# controller-board.net
KiCad netlist of a schematic drawn in EAGLE
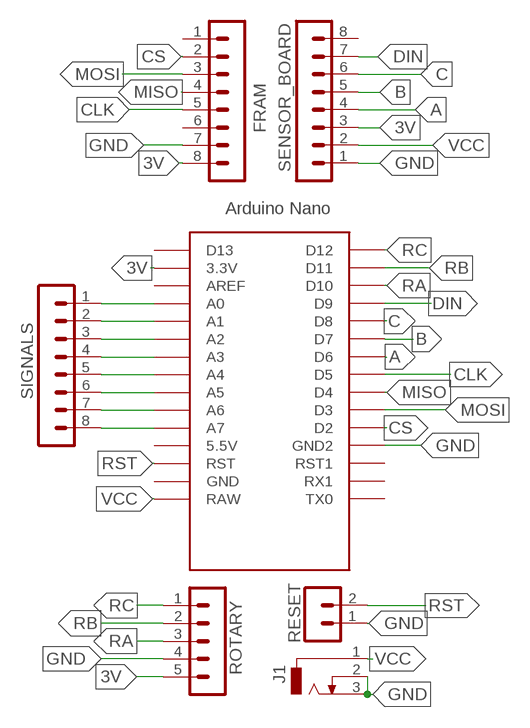
[diagram p0: schematic, sheet 1]

(export (version "E")
  (design (tool "Eeschema 10.0.6"))
  (components
    (comp (ref "ANALOG")
      (value "SIGNALS")
      (footprint "eagle-import:MA08-1")
      (libsource (lib "eagle-import") (part "MA08-1"))
    )
    (comp (ref "FRAM")
      (value "FRAM")
      (footprint "eagle-import:MA08-1")
      (libsource (lib "eagle-import") (part "MA08-1"))
    )
    (comp (ref "J1")
      (value "DCJ0202")
      (footprint "eagle-import:DCJ0202")
      (libsource (lib "eagle-import") (part "DCJ0202"))
    )
    (comp (ref "RESET")
      (value "B2B-PH-K")
      (footprint "eagle-import:B2B-PH-K")
      (libsource (lib "eagle-import") (part "B2B-PH-K"))
    )
    (comp (ref "ROTARY")
      (value "B5B-PH-K")
      (footprint "eagle-import:B5B-PH-K")
      (libsource (lib "eagle-import") (part "B5B-PH-K"))
    )
    (comp (ref "SV2")
      (value "SENSOR_BOARD")
      (footprint "eagle-import:MA08-1")
      (libsource (lib "eagle-import") (part "MA08-1"))
    )
    (comp (ref "U$1")
      (value "NANO")
      (footprint "eagle-import:NANO")
      (libsource (lib "eagle-import") (part "NANO"))
    )
  )
  (nets
    (net (code "1") (name "3V") (class "Default")
      (node (ref "FRAM") (pin "8") (pinfunction "8_8") (pintype "passive"))
      (node (ref "ROTARY") (pin "5") (pinfunction "5_5") (pintype "passive"))
      (node (ref "SV2") (pin "3") (pinfunction "3_3") (pintype "passive"))
      (node (ref "U$1") (pin "3.3V") (pinfunction "3.3V_3.3V") (pintype "bidirectional"))
    )
    (net (code "2") (name "A") (class "Default")
      (node (ref "SV2") (pin "4") (pinfunction "4_4") (pintype "passive"))
      (node (ref "U$1") (pin "D6") (pinfunction "D6_D6") (pintype "bidirectional"))
    )
    (net (code "3") (name "B") (class "Default")
      (node (ref "SV2") (pin "5") (pinfunction "5_5") (pintype "passive"))
      (node (ref "U$1") (pin "D7") (pinfunction "D7_D7") (pintype "bidirectional"))
    )
    (net (code "4") (name "C") (class "Default")
      (node (ref "SV2") (pin "6") (pinfunction "6_6") (pintype "passive"))
      (node (ref "U$1") (pin "D8") (pinfunction "D8_D8") (pintype "bidirectional"))
    )
    (net (code "5") (name "CLK") (class "Default")
      (node (ref "FRAM") (pin "5") (pinfunction "5_5") (pintype "passive"))
      (node (ref "U$1") (pin "D5") (pinfunction "D5_D5") (pintype "bidirectional"))
    )
    (net (code "6") (name "CS") (class "Default")
      (node (ref "FRAM") (pin "2") (pinfunction "2_2") (pintype "passive"))
      (node (ref "U$1") (pin "D2") (pinfunction "D2_D2") (pintype "bidirectional"))
    )
    (net (code "7") (name "DIN") (class "Default")
      (node (ref "SV2") (pin "7") (pinfunction "7_7") (pintype "passive"))
      (node (ref "U$1") (pin "D9") (pinfunction "D9_D9") (pintype "bidirectional"))
    )
    (net (code "8") (name "GND") (class "Default")
      (node (ref "FRAM") (pin "7") (pinfunction "7_7") (pintype "passive"))
      (node (ref "J1") (pin "2") (pinfunction "2_2") (pintype "passive"))
      (node (ref "J1") (pin "3") (pinfunction "3_3") (pintype "passive"))
      (node (ref "RESET") (pin "1") (pinfunction "1_1") (pintype "passive"))
      (node (ref "ROTARY") (pin "4") (pinfunction "4_4") (pintype "passive"))
      (node (ref "SV2") (pin "1") (pinfunction "1_1") (pintype "passive"))
      (node (ref "U$1") (pin "GND1") (pinfunction "GND2_GND1") (pintype "bidirectional"))
    )
    (net (code "9") (name "MISO") (class "Default")
      (node (ref "FRAM") (pin "4") (pinfunction "4_4") (pintype "passive"))
      (node (ref "U$1") (pin "D4") (pinfunction "D4_D4") (pintype "bidirectional"))
    )
    (net (code "10") (name "MOSI") (class "Default")
      (node (ref "FRAM") (pin "3") (pinfunction "3_3") (pintype "passive"))
      (node (ref "U$1") (pin "D3") (pinfunction "D3_D3") (pintype "bidirectional"))
    )
    (net (code "11") (name "Net-(ANALOG-Pad1)") (class "Default")
      (node (ref "ANALOG") (pin "1") (pinfunction "1_1") (pintype "passive"))
      (node (ref "U$1") (pin "A0") (pinfunction "A0_A0") (pintype "bidirectional"))
    )
    (net (code "12") (name "Net-(ANALOG-Pad2)") (class "Default")
      (node (ref "ANALOG") (pin "2") (pinfunction "2_2") (pintype "passive"))
      (node (ref "U$1") (pin "A1") (pinfunction "A1_A1") (pintype "bidirectional"))
    )
    (net (code "13") (name "Net-(ANALOG-Pad3)") (class "Default")
      (node (ref "ANALOG") (pin "3") (pinfunction "3_3") (pintype "passive"))
      (node (ref "U$1") (pin "A2") (pinfunction "A2_A2") (pintype "bidirectional"))
    )
    (net (code "14") (name "Net-(ANALOG-Pad4)") (class "Default")
      (node (ref "ANALOG") (pin "4") (pinfunction "4_4") (pintype "passive"))
      (node (ref "U$1") (pin "A3") (pinfunction "A3_A3") (pintype "bidirectional"))
    )
    (net (code "15") (name "Net-(ANALOG-Pad5)") (class "Default")
      (node (ref "ANALOG") (pin "5") (pinfunction "5_5") (pintype "passive"))
      (node (ref "U$1") (pin "A4") (pinfunction "A4_A4") (pintype "bidirectional"))
    )
    (net (code "16") (name "Net-(ANALOG-Pad6)") (class "Default")
      (node (ref "ANALOG") (pin "6") (pinfunction "6_6") (pintype "passive"))
      (node (ref "U$1") (pin "A5") (pinfunction "A5_A5") (pintype "bidirectional"))
    )
    (net (code "17") (name "Net-(ANALOG-Pad7)") (class "Default")
      (node (ref "ANALOG") (pin "7") (pinfunction "7_7") (pintype "passive"))
      (node (ref "U$1") (pin "A6") (pinfunction "A6_A6") (pintype "bidirectional"))
    )
    (net (code "18") (name "Net-(ANALOG-Pad8)") (class "Default")
      (node (ref "ANALOG") (pin "8") (pinfunction "8_8") (pintype "passive"))
      (node (ref "U$1") (pin "A7") (pinfunction "A7_A7") (pintype "bidirectional"))
    )
    (net (code "19") (name "RA") (class "Default")
      (node (ref "ROTARY") (pin "3") (pinfunction "3_3") (pintype "passive"))
      (node (ref "U$1") (pin "D10") (pinfunction "D10_D10") (pintype "bidirectional"))
    )
    (net (code "20") (name "RB") (class "Default")
      (node (ref "ROTARY") (pin "2") (pinfunction "2_2") (pintype "passive"))
      (node (ref "U$1") (pin "D11") (pinfunction "D11_D11") (pintype "bidirectional"))
    )
    (net (code "21") (name "RC") (class "Default")
      (node (ref "ROTARY") (pin "1") (pinfunction "1_1") (pintype "passive"))
      (node (ref "U$1") (pin "D12") (pinfunction "D12_D12") (pintype "bidirectional"))
    )
    (net (code "22") (name "RST") (class "Default")
      (node (ref "RESET") (pin "2") (pinfunction "2_2") (pintype "passive"))
      (node (ref "U$1") (pin "RST") (pinfunction "RST_RST") (pintype "bidirectional"))
    )
    (net (code "23") (name "VCC") (class "Default")
      (node (ref "J1") (pin "1") (pinfunction "1_1") (pintype "passive"))
      (node (ref "SV2") (pin "2") (pinfunction "2_2") (pintype "passive"))
      (node (ref "U$1") (pin "RAW") (pinfunction "RAW_RAW") (pintype "bidirectional"))
    )
    (net (code "24") (name "unconnected-(FRAM-Pad1)") (class "Default")
      (node (ref "FRAM") (pin "1") (pinfunction "1_1") (pintype "passive"))
    )
    (net (code "25") (name "unconnected-(FRAM-Pad6)") (class "Default")
      (node (ref "FRAM") (pin "6") (pinfunction "6_6") (pintype "passive"))
    )
    (net (code "26") (name "unconnected-(SV2-Pad8)") (class "Default")
      (node (ref "SV2") (pin "8") (pinfunction "8_8") (pintype "passive"))
    )
    (net (code "27") (name "unconnected-(U$1-5.5V-Pad5V)") (class "Default")
      (node (ref "U$1") (pin "5V") (pinfunction "5.5V_5V") (pintype "bidirectional"))
    )
    (net (code "28") (name "unconnected-(U$1-PadAREF)") (class "Default")
      (node (ref "U$1") (pin "AREF") (pinfunction "AREF_AREF") (pintype "bidirectional"))
    )
    (net (code "29") (name "unconnected-(U$1-PadD13)") (class "Default")
      (node (ref "U$1") (pin "D13") (pinfunction "D13_D13") (pintype "bidirectional"))
    )
    (net (code "30") (name "unconnected-(U$1-PadGND)") (class "Default")
      (node (ref "U$1") (pin "GND") (pinfunction "GND_GND") (pintype "bidirectional"))
    )
    (net (code "31") (name "unconnected-(U$1-PadICSP1)") (class "Default")
      (node (ref "U$1") (pin "ICSP1") (pinfunction "ICSP1_ICSP1") (pintype "bidirectional"))
    )
    (net (code "32") (name "unconnected-(U$1-PadICSP2)") (class "Default")
      (node (ref "U$1") (pin "ICSP2") (pinfunction "ICSP2_ICSP2") (pintype "bidirectional"))
    )
    (net (code "33") (name "unconnected-(U$1-PadICSP3)") (class "Default")
      (node (ref "U$1") (pin "ICSP3") (pinfunction "ICSP3_ICSP3") (pintype "bidirectional"))
    )
    (net (code "34") (name "unconnected-(U$1-PadICSP4)") (class "Default")
      (node (ref "U$1") (pin "ICSP4") (pinfunction "ICSP4_ICSP4") (pintype "bidirectional"))
    )
    (net (code "35") (name "unconnected-(U$1-PadICSP5)") (class "Default")
      (node (ref "U$1") (pin "ICSP5") (pinfunction "ICSP5_ICSP5") (pintype "bidirectional"))
    )
    (net (code "36") (name "unconnected-(U$1-PadICSP6)") (class "Default")
      (node (ref "U$1") (pin "ICSP6") (pinfunction "ICSP6_ICSP6") (pintype "bidirectional"))
    )
    (net (code "37") (name "unconnected-(U$1-PadRST1)") (class "Default")
      (node (ref "U$1") (pin "RST1") (pinfunction "RST1_RST1") (pintype "bidirectional"))
    )
    (net (code "38") (name "unconnected-(U$1-PadRX1)") (class "Default")
      (node (ref "U$1") (pin "RX1") (pinfunction "RX1_RX1") (pintype "bidirectional"))
    )
    (net (code "39") (name "unconnected-(U$1-PadTX0)") (class "Default")
      (node (ref "U$1") (pin "TX0") (pinfunction "TX0_TX0") (pintype "bidirectional"))
    )
  )
)
